# TLE8209-2SA.net
KiCad netlist of a schematic drawn in Altium Designer
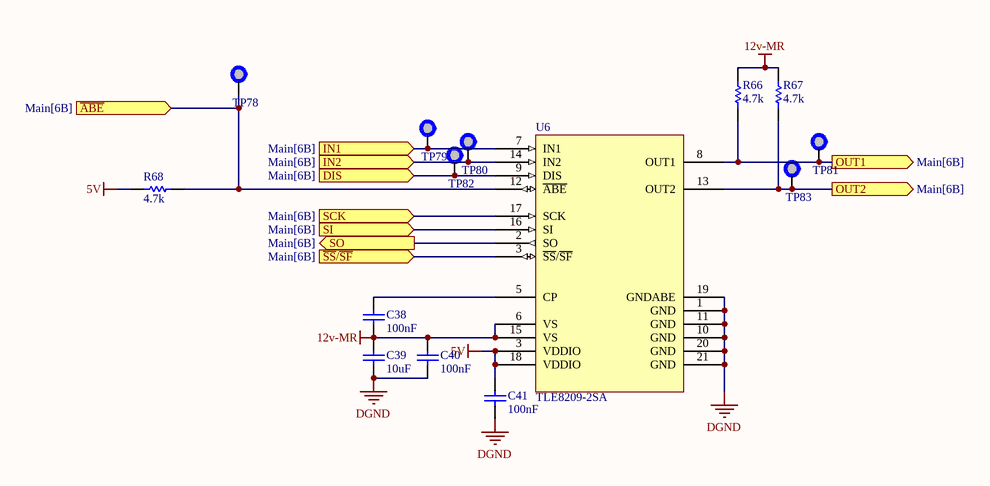
[diagram p0: TLE8209-2SA.SchDoc]

(export (version "E")
  (design (tool "Eeschema 10.0.6"))
  (components
    (comp (ref "C38")
      (value "100nF")
      (footprint "0603c")
      (description "LOW ESR")
      (fields (field (name "PUBLISHER") "Altium Limited"))
      (libsource (lib "Miscellaneous Devices") (part "Cap"))
    )
    (comp (ref "C39")
      (value "10uF")
      (footprint "1206C")
      (description "Low ESR")
      (fields (field (name "Comment") "10uf/50V") (field (name "PUBLISHER") "Altium Limited"))
      (libsource (lib "Miscellaneous Devices") (part "Cap"))
    )
    (comp (ref "C40")
      (value "100nF")
      (footprint "0603c")
      (description "LOW ESR")
      (fields (field (name "PUBLISHER") "Altium Limited"))
      (libsource (lib "Miscellaneous Devices") (part "Cap"))
    )
    (comp (ref "C41")
      (value "100nF")
      (footprint "0603c")
      (description "LOW ESR")
      (fields (field (name "PUBLISHER") "Altium Limited"))
      (libsource (lib "Miscellaneous Devices") (part "Cap"))
    )
    (comp (ref "R66")
      (value "4.7k")
      (footprint "0805")
      (description "Resistor")
      (fields (field (name "Comment") "4.7K") (field (name "PUBLISHER") "Altium Limited"))
      (libsource (lib "Miscellaneous Devices") (part "Res1"))
    )
    (comp (ref "R67")
      (value "4.7k")
      (footprint "0805")
      (description "Resistor")
      (fields (field (name "Comment") "4.7K") (field (name "PUBLISHER") "Altium Limited"))
      (libsource (lib "Miscellaneous Devices") (part "Res1"))
    )
    (comp (ref "R68")
      (value "4.7k")
      (footprint "0805")
      (description "Resistor")
      (fields (field (name "Comment") "4.7K") (field (name "PUBLISHER") "Altium Limited"))
      (libsource (lib "Miscellaneous Devices") (part "Res1"))
    )
    (comp (ref "TP78") (value "TestPoint") (footprint "TP") (libsource (lib "SchlibV0.1") (part "TestPoint")))
    (comp (ref "TP79") (value "TestPoint") (footprint "TP") (libsource (lib "SchlibV0.1") (part "TestPoint")))
    (comp (ref "TP80") (value "TestPoint") (footprint "TP") (libsource (lib "SchlibV0.1") (part "TestPoint")))
    (comp (ref "TP81") (value "TestPoint") (footprint "TP") (libsource (lib "SchlibV0.1") (part "TestPoint")))
    (comp (ref "TP82") (value "TestPoint") (footprint "TP") (libsource (lib "SchlibV0.1") (part "TestPoint")))
    (comp (ref "TP83") (value "TestPoint") (footprint "TP") (libsource (lib "SchlibV0.1") (part "TestPoint")))
    (comp (ref "U6")
      (value "TLE8209-2SA")
      (footprint "TLE8209-2SA")
      (libsource (lib "SchlibV0.1") (part "TLE8209-2SA"))
    )
  )
  (nets
    (net (code "1") (name "/DIS") (class "Default")
      (node (ref "TP82") (pin "1") (pintype "passive"))
      (node (ref "U6") (pin "9") (pinfunction "DIS_9") (pintype "input"))
    )
    (net (code "2") (name "/IN1") (class "Default")
      (node (ref "TP79") (pin "1") (pintype "passive"))
      (node (ref "U6") (pin "7") (pinfunction "IN1_7") (pintype "input"))
    )
    (net (code "3") (name "/IN2") (class "Default")
      (node (ref "TP80") (pin "1") (pintype "passive"))
      (node (ref "U6") (pin "14") (pinfunction "IN2_14") (pintype "input"))
    )
    (net (code "4") (name "/OUT1") (class "Default")
      (node (ref "R66") (pin "2") (pinfunction "2_2") (pintype "passive"))
      (node (ref "TP81") (pin "1") (pintype "passive"))
      (node (ref "U6") (pin "8") (pinfunction "OUT1_8") (pintype "passive"))
    )
    (net (code "5") (name "/OUT2") (class "Default")
      (node (ref "R67") (pin "2") (pinfunction "2_2") (pintype "passive"))
      (node (ref "TP83") (pin "1") (pintype "passive"))
      (node (ref "U6") (pin "13") (pinfunction "OUT2_13") (pintype "passive"))
    )
    (net (code "6") (name "/SCK") (class "Default")
      (node (ref "U6") (pin "17") (pinfunction "SCK_17") (pintype "input"))
    )
    (net (code "7") (name "/SI") (class "Default")
      (node (ref "U6") (pin "16") (pinfunction "SI_16") (pintype "input"))
    )
    (net (code "8") (name "/SO") (class "Default")
      (node (ref "U6") (pin "2") (pinfunction "SO_2") (pintype "output"))
    )
    (net (code "9") (name "/~{ABE}") (class "Default")
      (node (ref "R68") (pin "2") (pinfunction "2_2") (pintype "passive"))
      (node (ref "TP78") (pin "1") (pintype "passive"))
      (node (ref "U6") (pin "12") (pinfunction "~{ABE}_12") (pintype "bidirectional"))
    )
    (net (code "10") (name "/~{SS}{slash}~{SF}") (class "Default")
      (node (ref "U6") (pin "3") (pinfunction "~{SS}/~{SF}_3") (pintype "bidirectional"))
    )
    (net (code "11") (name "5V") (class "Default")
      (node (ref "C41") (pin "1") (pinfunction "1_1") (pintype "passive"))
      (node (ref "R68") (pin "1") (pinfunction "1_1") (pintype "passive"))
      (node (ref "U6") (pin "18") (pinfunction "VDDIO_18") (pintype "passive"))
      (node (ref "U6") (pin "3") (pinfunction "VDDIO_3") (pintype "passive"))
    )
    (net (code "12") (name "12v-MR") (class "Default")
      (node (ref "C38") (pin "2") (pinfunction "2_2") (pintype "passive"))
      (node (ref "C39") (pin "2") (pinfunction "2_2") (pintype "passive"))
      (node (ref "C40") (pin "1") (pinfunction "1_1") (pintype "passive"))
      (node (ref "R66") (pin "1") (pinfunction "1_1") (pintype "passive"))
      (node (ref "R67") (pin "1") (pinfunction "1_1") (pintype "passive"))
      (node (ref "U6") (pin "15") (pinfunction "VS_15") (pintype "passive"))
      (node (ref "U6") (pin "6") (pinfunction "VS_6") (pintype "passive"))
    )
    (net (code "13") (name "DGND") (class "Default")
      (node (ref "C39") (pin "1") (pinfunction "1_1") (pintype "passive"))
      (node (ref "C40") (pin "2") (pinfunction "2_2") (pintype "passive"))
      (node (ref "C41") (pin "2") (pinfunction "2_2") (pintype "passive"))
      (node (ref "U6") (pin "1") (pinfunction "GND_1") (pintype "passive"))
      (node (ref "U6") (pin "10") (pinfunction "GND_10") (pintype "passive"))
      (node (ref "U6") (pin "11") (pinfunction "GND_11") (pintype "passive"))
      (node (ref "U6") (pin "19") (pinfunction "GNDABE_19") (pintype "passive"))
      (node (ref "U6") (pin "20") (pinfunction "GND_20") (pintype "passive"))
      (node (ref "U6") (pin "21") (pinfunction "GND_21") (pintype "passive"))
    )
    (net (code "14") (name "Net-(U6-CP)") (class "Default")
      (node (ref "C38") (pin "1") (pinfunction "1_1") (pintype "passive"))
      (node (ref "U6") (pin "5") (pinfunction "CP_5") (pintype "passive"))
    )
  )
)
